# VGA-SCH.net
KiCad netlist of a schematic drawn in Altium Designer
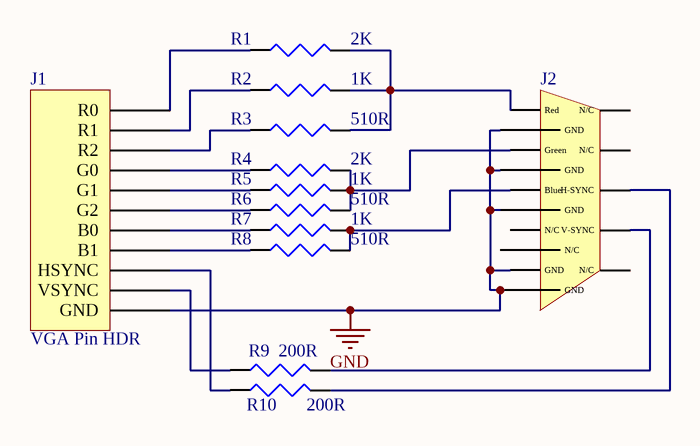
[diagram p0: VGA-SCH.SchDoc]

(export (version "E")
  (design (tool "Eeschema 10.0.6"))
  (components
    (comp (ref "J1")
      (value "VGA Pin HDR")
      (footprint "VGA HDR")
      (description "VGA pin male header")
      (libsource (lib "VGA-Module-SCH-LIB") (part "Connector{colon} VGA HDR"))
    )
    (comp (ref "J2")
      (value "Female DB15 VGA connector")
      (footprint "VGA CONNECTOR")
      (libsource (lib "VGA-Module-SCH-LIB") (part "Connector{colon} DB15 VGA"))
    )
    (comp (ref "R1")
      (value "2K")
      (footprint "Resistor 1206")
      (description "Res Thick Film 1206 2K Ohm 1% 1/4W ±100ppm/°C Molded SMD SMD Paper T/R")
      (fields
        (field (name "MANUFACTURER") "Yageo")
        (field (name "MANUFACTURER PART NUMBER") "RC1206FR-132KL")
      )
      (libsource (lib "VGA-Module-SCH-LIB") (part "Resistor{colon} 2K R"))
    )
    (comp (ref "R2")
      (value "1K")
      (footprint "Resistor 1206")
      (description "Res Thick Film 1206 1K Ohm 5% 1/4W ±100ppm/°C Molded SMD SMD Paper T/R")
      (fields
        (field (name "MANUFACTURER") "Yageo")
        (field (name "MANUFACTURER PART NUMBER") "RC1206JR-131KL")
      )
      (libsource (lib "VGA-Module-SCH-LIB") (part "Resistor{colon} 1K R"))
    )
    (comp (ref "R3")
      (value "510R")
      (footprint "Resistor 1206")
      (description "Res Thick Film 1206 510 Ohm 1% 1/4W ±100ppm/°C Molded SMD SMD Paper T/R")
      (fields
        (field (name "MANUFACTURER") "Vishay Dale")
        (field (name "MANUFACTURER PART NUMBER") "CRCW1206510RFKEB")
      )
      (libsource (lib "VGA-Module-SCH-LIB") (part "Resistor{colon} 510R"))
    )
    (comp (ref "R4")
      (value "2K")
      (footprint "Resistor 1206")
      (description "Res Thick Film 1206 2K Ohm 1% 1/4W ±100ppm/°C Molded SMD SMD Paper T/R")
      (fields
        (field (name "MANUFACTURER") "Yageo")
        (field (name "MANUFACTURER PART NUMBER") "RC1206FR-132KL")
      )
      (libsource (lib "VGA-Module-SCH-LIB") (part "Resistor{colon} 2K R"))
    )
    (comp (ref "R5")
      (value "1K")
      (footprint "Resistor 1206")
      (description "Res Thick Film 1206 1K Ohm 5% 1/4W ±100ppm/°C Molded SMD SMD Paper T/R")
      (fields
        (field (name "MANUFACTURER") "Yageo")
        (field (name "MANUFACTURER PART NUMBER") "RC1206JR-131KL")
      )
      (libsource (lib "VGA-Module-SCH-LIB") (part "Resistor{colon} 1K R"))
    )
    (comp (ref "R6")
      (value "510R")
      (footprint "Resistor 1206")
      (description "Res Thick Film 1206 510 Ohm 1% 1/4W ±100ppm/°C Molded SMD SMD Paper T/R")
      (fields
        (field (name "MANUFACTURER") "Vishay Dale")
        (field (name "MANUFACTURER PART NUMBER") "CRCW1206510RFKEB")
      )
      (libsource (lib "VGA-Module-SCH-LIB") (part "Resistor{colon} 510R"))
    )
    (comp (ref "R7")
      (value "1K")
      (footprint "Resistor 1206")
      (description "Res Thick Film 1206 1K Ohm 5% 1/4W ±100ppm/°C Molded SMD SMD Paper T/R")
      (fields
        (field (name "MANUFACTURER") "Yageo")
        (field (name "MANUFACTURER PART NUMBER") "RC1206JR-131KL")
      )
      (libsource (lib "VGA-Module-SCH-LIB") (part "Resistor{colon} 1K R"))
    )
    (comp (ref "R8")
      (value "510R")
      (footprint "Resistor 1206")
      (description "Res Thick Film 1206 510 Ohm 1% 1/4W ±100ppm/°C Molded SMD SMD Paper T/R")
      (fields
        (field (name "MANUFACTURER") "Vishay Dale")
        (field (name "MANUFACTURER PART NUMBER") "CRCW1206510RFKEB")
      )
      (libsource (lib "VGA-Module-SCH-LIB") (part "Resistor{colon} 510R"))
    )
    (comp (ref "R9")
      (value "200R")
      (footprint "Resistor 1206")
      (description "Surface Mount Thick Film Resistor, AEC-Q200 ERJ Series, 200 ohm, 250 mW, - 1%, 200 V")
      (fields
        (field (name "MANUFACTURER") "Panasonic")
        (field (name "MANUFACTURER PART NUMBER") "ERJ-U08F2000V")
      )
      (libsource (lib "VGA-Module-SCH-LIB") (part "Resistor{colon} 200R"))
    )
    (comp (ref "R10")
      (value "200R")
      (footprint "Resistor 1206")
      (description "Surface Mount Thick Film Resistor, AEC-Q200 ERJ Series, 200 ohm, 250 mW, - 1%, 200 V")
      (fields
        (field (name "MANUFACTURER") "Panasonic")
        (field (name "MANUFACTURER PART NUMBER") "ERJ-U08F2000V")
      )
      (libsource (lib "VGA-Module-SCH-LIB") (part "Resistor{colon} 200R"))
    )
  )
  (nets
    (net (code "1") (name "GND") (class "Default")
      (node (ref "J1") (pin "11") (pinfunction "GND_11") (pintype "passive"))
      (node (ref "J2") (pin "10") (pinfunction "GND_10") (pintype "passive"))
      (node (ref "J2") (pin "5") (pinfunction "GND_5") (pintype "passive"))
      (node (ref "J2") (pin "6") (pinfunction "GND_6") (pintype "passive"))
      (node (ref "J2") (pin "7") (pinfunction "GND_7") (pintype "passive"))
      (node (ref "J2") (pin "8") (pinfunction "GND_8") (pintype "passive"))
    )
    (net (code "2") (name "Net-(J1-B0)") (class "Default")
      (node (ref "J1") (pin "7") (pinfunction "B0_7") (pintype "passive"))
      (node (ref "R7") (pin "1") (pinfunction "1_1") (pintype "passive"))
    )
    (net (code "3") (name "Net-(J1-B1)") (class "Default")
      (node (ref "J1") (pin "8") (pinfunction "B1_8") (pintype "passive"))
      (node (ref "R8") (pin "1") (pinfunction "1_1") (pintype "passive"))
    )
    (net (code "4") (name "Net-(J1-G0)") (class "Default")
      (node (ref "J1") (pin "4") (pinfunction "G0_4") (pintype "passive"))
      (node (ref "R4") (pin "1") (pinfunction "1_1") (pintype "passive"))
    )
    (net (code "5") (name "Net-(J1-G1)") (class "Default")
      (node (ref "J1") (pin "5") (pinfunction "G1_5") (pintype "passive"))
      (node (ref "R5") (pin "1") (pinfunction "1_1") (pintype "passive"))
    )
    (net (code "6") (name "Net-(J1-G2)") (class "Default")
      (node (ref "J1") (pin "6") (pinfunction "G2_6") (pintype "passive"))
      (node (ref "R6") (pin "1") (pinfunction "1_1") (pintype "passive"))
    )
    (net (code "7") (name "Net-(J1-HSYNC)") (class "Default")
      (node (ref "J1") (pin "9") (pinfunction "HSYNC_9") (pintype "passive"))
      (node (ref "R10") (pin "1") (pinfunction "1_1") (pintype "passive"))
    )
    (net (code "8") (name "Net-(J1-R0)") (class "Default")
      (node (ref "J1") (pin "1") (pinfunction "R0_1") (pintype "passive"))
      (node (ref "R1") (pin "1") (pinfunction "1_1") (pintype "passive"))
    )
    (net (code "9") (name "Net-(J1-R1)") (class "Default")
      (node (ref "J1") (pin "2") (pinfunction "R1_2") (pintype "passive"))
      (node (ref "R2") (pin "1") (pinfunction "1_1") (pintype "passive"))
    )
    (net (code "10") (name "Net-(J1-R2)") (class "Default")
      (node (ref "J1") (pin "3") (pinfunction "R2_3") (pintype "passive"))
      (node (ref "R3") (pin "1") (pinfunction "1_1") (pintype "passive"))
    )
    (net (code "11") (name "Net-(J1-VSYNC)") (class "Default")
      (node (ref "J1") (pin "10") (pinfunction "VSYNC_10") (pintype "passive"))
      (node (ref "R9") (pin "1") (pinfunction "1_1") (pintype "passive"))
    )
    (net (code "12") (name "Net-(J2-Blue)") (class "Default")
      (node (ref "J2") (pin "3") (pinfunction "Blue_3") (pintype "passive"))
      (node (ref "R7") (pin "2") (pinfunction "2_2") (pintype "passive"))
      (node (ref "R8") (pin "2") (pinfunction "2_2") (pintype "passive"))
    )
    (net (code "13") (name "Net-(J2-Green)") (class "Default")
      (node (ref "J2") (pin "2") (pinfunction "Green_2") (pintype "passive"))
      (node (ref "R4") (pin "2") (pinfunction "2_2") (pintype "passive"))
      (node (ref "R5") (pin "2") (pinfunction "2_2") (pintype "passive"))
      (node (ref "R6") (pin "2") (pinfunction "2_2") (pintype "passive"))
    )
    (net (code "14") (name "Net-(J2-H-SYNC)") (class "Default")
      (node (ref "J2") (pin "13") (pinfunction "H-SYNC_13") (pintype "passive"))
      (node (ref "R10") (pin "2") (pinfunction "2_2") (pintype "passive"))
    )
    (net (code "15") (name "Net-(J2-Red)") (class "Default")
      (node (ref "J2") (pin "1") (pinfunction "Red_1") (pintype "passive"))
      (node (ref "R1") (pin "2") (pinfunction "2_2") (pintype "passive"))
      (node (ref "R2") (pin "2") (pinfunction "2_2") (pintype "passive"))
      (node (ref "R3") (pin "2") (pinfunction "2_2") (pintype "passive"))
    )
    (net (code "16") (name "Net-(J2-V-SYNC)") (class "Default")
      (node (ref "J2") (pin "14") (pinfunction "V-SYNC_14") (pintype "passive"))
      (node (ref "R9") (pin "2") (pinfunction "2_2") (pintype "passive"))
    )
    (net (code "17") (name "unconnected-(J2-N{slash}C-Pad4)") (class "Default")
      (node (ref "J2") (pin "4") (pinfunction "N/C_4") (pintype "passive"))
    )
    (net (code "18") (name "unconnected-(J2-N{slash}C-Pad9)") (class "Default")
      (node (ref "J2") (pin "9") (pinfunction "N/C_9") (pintype "passive"))
    )
    (net (code "19") (name "unconnected-(J2-N{slash}C-Pad11)") (class "Default")
      (node (ref "J2") (pin "11") (pinfunction "N/C_11") (pintype "passive"))
    )
    (net (code "20") (name "unconnected-(J2-N{slash}C-Pad12)") (class "Default")
      (node (ref "J2") (pin "12") (pinfunction "N/C_12") (pintype "passive"))
    )
    (net (code "21") (name "unconnected-(J2-N{slash}C-Pad15)") (class "Default")
      (node (ref "J2") (pin "15") (pinfunction "N/C_15") (pintype "passive"))
    )
  )
)
